# Beacon_controller_ESP32.net
KiCad netlist of a schematic drawn in EAGLE
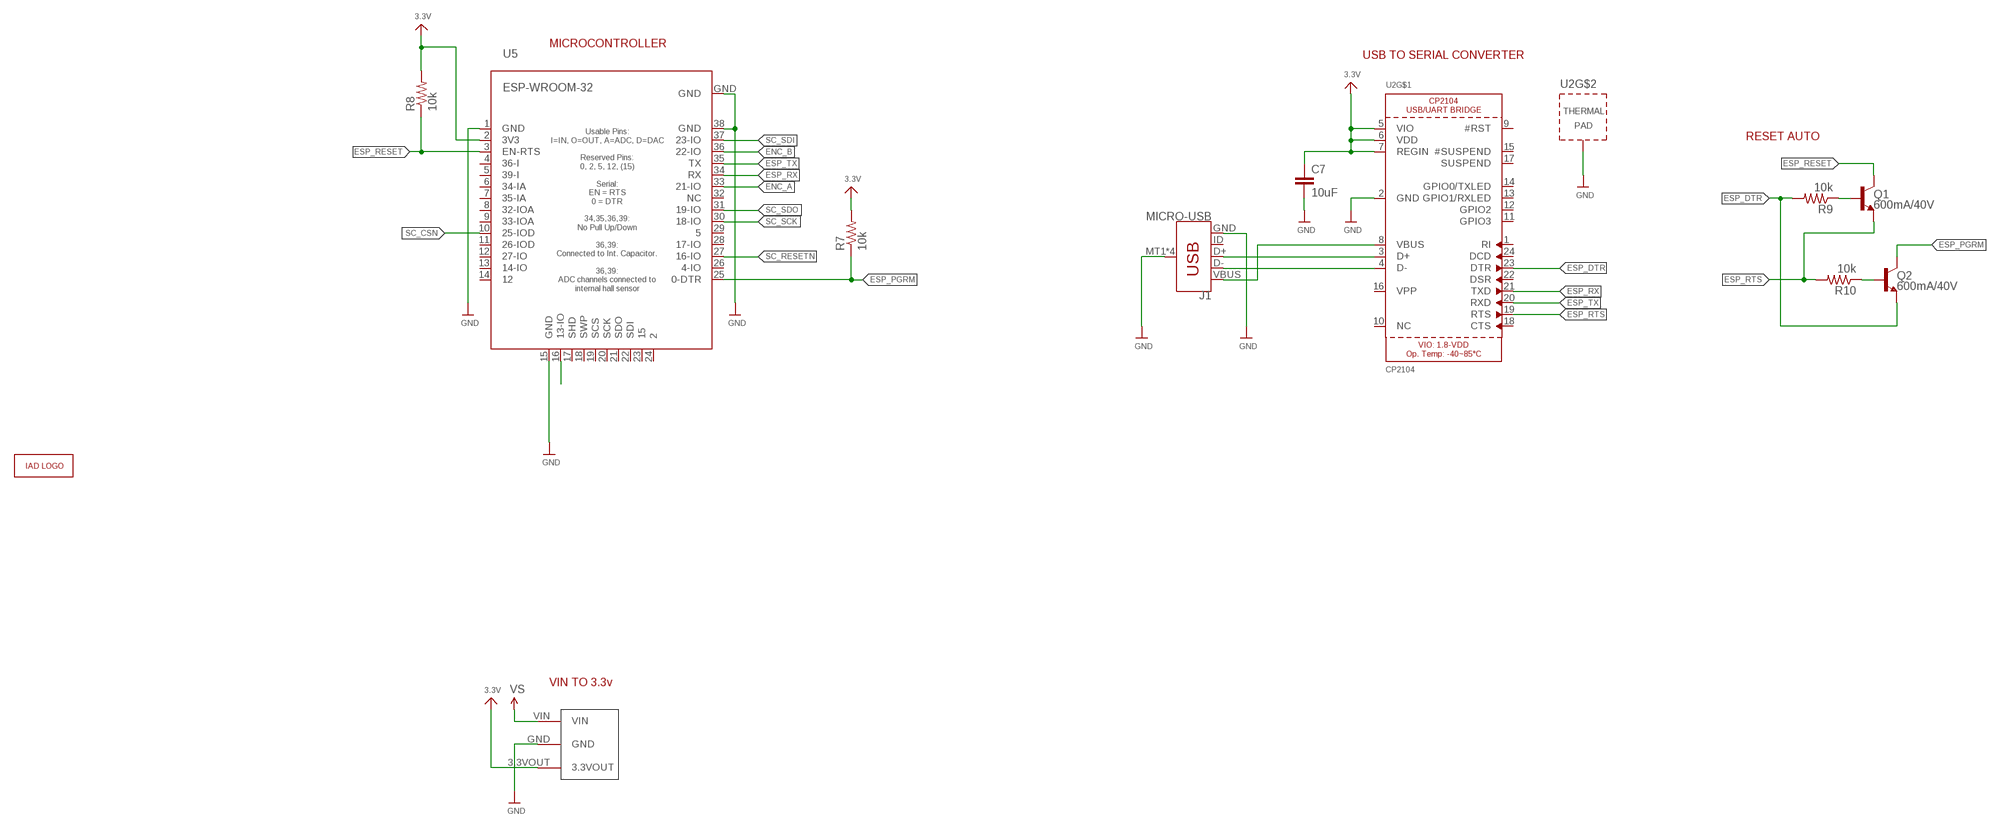
[diagram p0: schematic, sheet 1]

(export (version "E")
  (design (tool "Eeschema 10.0.6"))
  (components
    (comp (ref "A1")
      (value "ZHDK_LOGO_METAL")
      (footprint "eagle-import:ZHDK_LOGO")
      (libsource (lib "eagle-import") (part "ZHDK_LOGO_METAL"))
    )
    (comp (ref "C7")
      (value "10uF")
      (footprint "eagle-import:0603")
      (libsource (lib "eagle-import") (part "10UF-0603-6.3V-20%"))
    )
    (comp (ref "J1")
      (value "MICRO-USB")
      (footprint "eagle-import:USB-MICROB")
      (libsource (lib "eagle-import") (part "USB_MICRO-B_SMT"))
    )
    (comp (ref "Q1")
      (value "600mA/40V")
      (footprint "eagle-import:SOT23-3")
      (libsource (lib "eagle-import") (part "TRANS_NPN-MMBT2222AL"))
    )
    (comp (ref "Q2")
      (value "600mA/40V")
      (footprint "eagle-import:SOT23-3")
      (libsource (lib "eagle-import") (part "TRANS_NPN-MMBT2222AL"))
    )
    (comp (ref "R7")
      (value "10k")
      (footprint "eagle-import:0603-RES")
      (libsource (lib "eagle-import") (part "RESISTOR0603-RES"))
    )
    (comp (ref "R8")
      (value "10k")
      (footprint "eagle-import:0603-RES")
      (libsource (lib "eagle-import") (part "RESISTOR0603-RES"))
    )
    (comp (ref "R9")
      (value "10k")
      (footprint "eagle-import:0603-RES")
      (libsource (lib "eagle-import") (part "RESISTOR0603-RES"))
    )
    (comp (ref "R10")
      (value "10k")
      (footprint "eagle-import:0603-RES")
      (libsource (lib "eagle-import") (part "RESISTOR0603-RES"))
    )
    (comp (ref "U2")
      (value "CP2104")
      (footprint "eagle-import:QFN24_4MM_SMSC")
      (libsource (lib "eagle-import") (part "CP2104"))
    )
    (comp (ref "U4")
      (value "TRACO12433")
      (footprint "eagle-import:TRACO12433")
      (libsource (lib "eagle-import") (part "TRACO12433"))
    )
    (comp (ref "U5")
      (value "ESP-WROOM-32")
      (footprint "eagle-import:ESP-WROOM-32")
      (libsource (lib "eagle-import") (part "ESP-WROOM-32"))
    )
  )
  (nets
    (net (code "1") (name "3.3V") (class "Default")
      (node (ref "C7") (pin "1") (pinfunction "1_1") (pintype "passive"))
      (node (ref "R7") (pin "2") (pinfunction "2_2") (pintype "passive"))
      (node (ref "R8") (pin "2") (pinfunction "2_2") (pintype "passive"))
      (node (ref "U2") (pin "5") (pinfunction "VIO_5") (pintype "power_in"))
      (node (ref "U2") (pin "6") (pinfunction "VDD_6") (pintype "power_in"))
      (node (ref "U2") (pin "7") (pinfunction "REGIN_7") (pintype "power_in"))
      (node (ref "U4") (pin "3.3VOUT") (pinfunction "3.3VOUT_3.3VOUT") (pintype "bidirectional"))
      (node (ref "U5") (pin "2") (pinfunction "3V3_2") (pintype "bidirectional"))
    )
    (net (code "2") (name "ENC_A") (class "Default")
      (node (ref "U5") (pin "33") (pinfunction "21-IO_33") (pintype "bidirectional"))
    )
    (net (code "3") (name "ENC_B") (class "Default")
      (node (ref "U5") (pin "36") (pinfunction "22-IO_36") (pintype "bidirectional"))
    )
    (net (code "4") (name "ESP_DTR") (class "Default")
      (node (ref "Q2") (pin "2") (pinfunction "E_2") (pintype "passive"))
      (node (ref "R9") (pin "2") (pinfunction "2_2") (pintype "passive"))
      (node (ref "U2") (pin "23") (pinfunction "DTR_23") (pintype "output"))
    )
    (net (code "5") (name "ESP_PGRM") (class "Default")
      (node (ref "Q2") (pin "3") (pinfunction "C_3") (pintype "passive"))
      (node (ref "R7") (pin "1") (pinfunction "1_1") (pintype "passive"))
      (node (ref "U5") (pin "25") (pinfunction "0-DTR_25") (pintype "bidirectional"))
    )
    (net (code "6") (name "ESP_RESET") (class "Default")
      (node (ref "Q1") (pin "3") (pinfunction "C_3") (pintype "passive"))
      (node (ref "R8") (pin "1") (pinfunction "1_1") (pintype "passive"))
      (node (ref "U5") (pin "3") (pinfunction "EN-RTS_3") (pintype "bidirectional"))
    )
    (net (code "7") (name "ESP_RTS") (class "Default")
      (node (ref "Q1") (pin "2") (pinfunction "E_2") (pintype "passive"))
      (node (ref "R10") (pin "2") (pinfunction "2_2") (pintype "passive"))
      (node (ref "U2") (pin "19") (pinfunction "RTS_19") (pintype "output"))
    )
    (net (code "8") (name "ESP_RX") (class "Default")
      (node (ref "U2") (pin "21") (pinfunction "TXD_21") (pintype "output"))
      (node (ref "U5") (pin "34") (pinfunction "RX_34") (pintype "bidirectional"))
    )
    (net (code "9") (name "ESP_TX") (class "Default")
      (node (ref "U2") (pin "20") (pinfunction "RXD_20") (pintype "input"))
      (node (ref "U5") (pin "35") (pinfunction "TX_35") (pintype "bidirectional"))
    )
    (net (code "10") (name "GND") (class "Default")
      (node (ref "C7") (pin "2") (pinfunction "2_2") (pintype "passive"))
      (node (ref "J1") (pin "GND") (pinfunction "GND_GND") (pintype "power_in"))
      (node (ref "J1") (pin "MT1") (pinfunction "SHIELD_MT1") (pintype "bidirectional"))
      (node (ref "J1") (pin "MT2") (pinfunction "SHIELD_MT2") (pintype "bidirectional"))
      (node (ref "J1") (pin "P$1") (pinfunction "SHIELD_P$1") (pintype "bidirectional"))
      (node (ref "J1") (pin "P$2") (pinfunction "SHIELD_P$2") (pintype "bidirectional"))
      (node (ref "U2") (pin "2") (pinfunction "GND_2") (pintype "power_in"))
      (node (ref "U2") (pin "THERM") (pinfunction "TP_THERM") (pintype "power_in"))
      (node (ref "U4") (pin "GND") (pinfunction "GND_GND") (pintype "bidirectional"))
      (node (ref "U5") (pin "1") (pinfunction "GND_1") (pintype "bidirectional"))
      (node (ref "U5") (pin "15") (pinfunction "GND_15") (pintype "bidirectional"))
      (node (ref "U5") (pin "38") (pinfunction "GND_38") (pintype "bidirectional"))
      (node (ref "U5") (pin "GND") (pinfunction "GND_GND") (pintype "bidirectional"))
    )
    (net (code "11") (name "Net-(Q1-B)") (class "Default")
      (node (ref "Q1") (pin "1") (pinfunction "B_1") (pintype "passive"))
      (node (ref "R9") (pin "1") (pinfunction "1_1") (pintype "passive"))
    )
    (net (code "12") (name "Net-(Q2-B)") (class "Default")
      (node (ref "Q2") (pin "1") (pinfunction "B_1") (pintype "passive"))
      (node (ref "R10") (pin "1") (pinfunction "1_1") (pintype "passive"))
    )
    (net (code "13") (name "Net-(U2A-D+)") (class "Default")
      (node (ref "J1") (pin "D+") (pinfunction "D+_D+") (pintype "bidirectional"))
      (node (ref "U2") (pin "3") (pinfunction "D+_3") (pintype "bidirectional"))
    )
    (net (code "14") (name "Net-(U2A-D-)") (class "Default")
      (node (ref "J1") (pin "D-") (pinfunction "D-_D-") (pintype "bidirectional"))
      (node (ref "U2") (pin "4") (pinfunction "D-_4") (pintype "bidirectional"))
    )
    (net (code "15") (name "Net-(U2A-VBUS)") (class "Default")
      (node (ref "J1") (pin "VBUS") (pinfunction "VBUS_VBUS") (pintype "power_in"))
      (node (ref "U2") (pin "8") (pinfunction "VBUS_8") (pintype "power_in"))
    )
    (net (code "16") (name "SC_CSN") (class "Default")
      (node (ref "U5") (pin "10") (pinfunction "25-IOD_10") (pintype "bidirectional"))
    )
    (net (code "17") (name "SC_RESETN") (class "Default")
      (node (ref "U5") (pin "27") (pinfunction "16-IO_27") (pintype "bidirectional"))
    )
    (net (code "18") (name "SC_SCK") (class "Default")
      (node (ref "U5") (pin "30") (pinfunction "18-IO_30") (pintype "bidirectional"))
    )
    (net (code "19") (name "SC_SDI") (class "Default")
      (node (ref "U5") (pin "37") (pinfunction "23-IO_37") (pintype "bidirectional"))
    )
    (net (code "20") (name "SC_SDO") (class "Default")
      (node (ref "U5") (pin "31") (pinfunction "19-IO_31") (pintype "bidirectional"))
    )
    (net (code "21") (name "VS") (class "Default")
      (node (ref "U4") (pin "VIN") (pinfunction "VIN_VIN") (pintype "bidirectional"))
    )
    (net (code "22") (name "unconnected-(J1-PadID)") (class "Default")
      (node (ref "J1") (pin "ID") (pinfunction "ID_ID") (pintype "bidirectional"))
    )
    (net (code "23") (name "unconnected-(U2A-#RST-Pad9)") (class "Default")
      (node (ref "U2") (pin "9") (pinfunction "#RST_9") (pintype "bidirectional"))
    )
    (net (code "24") (name "unconnected-(U2A-#SUSPEND-Pad15)") (class "Default")
      (node (ref "U2") (pin "15") (pinfunction "#SUSPEND_15") (pintype "output"))
    )
    (net (code "25") (name "unconnected-(U2A-CTS-Pad18)") (class "Default")
      (node (ref "U2") (pin "18") (pinfunction "CTS_18") (pintype "input"))
    )
    (net (code "26") (name "unconnected-(U2A-DCD-Pad24)") (class "Default")
      (node (ref "U2") (pin "24") (pinfunction "DCD_24") (pintype "input"))
    )
    (net (code "27") (name "unconnected-(U2A-DSR-Pad22)") (class "Default")
      (node (ref "U2") (pin "22") (pinfunction "DSR_22") (pintype "input"))
    )
    (net (code "28") (name "unconnected-(U2A-GPIO0{slash}TXLED-Pad14)") (class "Default")
      (node (ref "U2") (pin "14") (pinfunction "GPIO0/TXLED_14") (pintype "bidirectional"))
    )
    (net (code "29") (name "unconnected-(U2A-GPIO1{slash}RXLED-Pad13)") (class "Default")
      (node (ref "U2") (pin "13") (pinfunction "GPIO1/RXLED_13") (pintype "bidirectional"))
    )
    (net (code "30") (name "unconnected-(U2A-GPIO2-Pad12)") (class "Default")
      (node (ref "U2") (pin "12") (pinfunction "GPIO2_12") (pintype "bidirectional"))
    )
    (net (code "31") (name "unconnected-(U2A-GPIO3-Pad11)") (class "Default")
      (node (ref "U2") (pin "11") (pinfunction "GPIO3_11") (pintype "bidirectional"))
    )
    (net (code "32") (name "unconnected-(U2A-NC-Pad10)") (class "Default")
      (node (ref "U2") (pin "10") (pinfunction "NC_10") (pintype "no_connect"))
    )
    (net (code "33") (name "unconnected-(U2A-RI-Pad1)") (class "Default")
      (node (ref "U2") (pin "1") (pinfunction "RI_1") (pintype "input"))
    )
    (net (code "34") (name "unconnected-(U2A-SUSPEND-Pad17)") (class "Default")
      (node (ref "U2") (pin "17") (pinfunction "SUSPEND_17") (pintype "output"))
    )
    (net (code "35") (name "unconnected-(U2A-VPP-Pad16)") (class "Default")
      (node (ref "U2") (pin "16") (pinfunction "VPP_16") (pintype "bidirectional"))
    )
    (net (code "36") (name "unconnected-(U5-2-Pad24)") (class "Default")
      (node (ref "U5") (pin "24") (pinfunction "2_24") (pintype "bidirectional"))
    )
    (net (code "37") (name "unconnected-(U5-4-IO-Pad26)") (class "Default")
      (node (ref "U5") (pin "26") (pinfunction "4-IO_26") (pintype "bidirectional"))
    )
    (net (code "38") (name "unconnected-(U5-5-Pad29)") (class "Default")
      (node (ref "U5") (pin "29") (pinfunction "5_29") (pintype "bidirectional"))
    )
    (net (code "39") (name "unconnected-(U5-12-Pad14)") (class "Default")
      (node (ref "U5") (pin "14") (pinfunction "12_14") (pintype "bidirectional"))
    )
    (net (code "40") (name "unconnected-(U5-13-IO-Pad16)") (class "Default")
      (node (ref "U5") (pin "16") (pinfunction "13-IO_16") (pintype "bidirectional"))
    )
    (net (code "41") (name "unconnected-(U5-14-IO-Pad13)") (class "Default")
      (node (ref "U5") (pin "13") (pinfunction "14-IO_13") (pintype "bidirectional"))
    )
    (net (code "42") (name "unconnected-(U5-15-Pad23)") (class "Default")
      (node (ref "U5") (pin "23") (pinfunction "15_23") (pintype "bidirectional"))
    )
    (net (code "43") (name "unconnected-(U5-17-IO-Pad28)") (class "Default")
      (node (ref "U5") (pin "28") (pinfunction "17-IO_28") (pintype "bidirectional"))
    )
    (net (code "44") (name "unconnected-(U5-26-IOD-Pad11)") (class "Default")
      (node (ref "U5") (pin "11") (pinfunction "26-IOD_11") (pintype "bidirectional"))
    )
    (net (code "45") (name "unconnected-(U5-27-IO-Pad12)") (class "Default")
      (node (ref "U5") (pin "12") (pinfunction "27-IO_12") (pintype "bidirectional"))
    )
    (net (code "46") (name "unconnected-(U5-32-IOA-Pad8)") (class "Default")
      (node (ref "U5") (pin "8") (pinfunction "32-IOA_8") (pintype "bidirectional"))
    )
    (net (code "47") (name "unconnected-(U5-33-IOA-Pad9)") (class "Default")
      (node (ref "U5") (pin "9") (pinfunction "33-IOA_9") (pintype "bidirectional"))
    )
    (net (code "48") (name "unconnected-(U5-34-IA-Pad6)") (class "Default")
      (node (ref "U5") (pin "6") (pinfunction "34-IA_6") (pintype "bidirectional"))
    )
    (net (code "49") (name "unconnected-(U5-35-IA-Pad7)") (class "Default")
      (node (ref "U5") (pin "7") (pinfunction "35-IA_7") (pintype "bidirectional"))
    )
    (net (code "50") (name "unconnected-(U5-36-I-Pad4)") (class "Default")
      (node (ref "U5") (pin "4") (pinfunction "36-I_4") (pintype "bidirectional"))
    )
    (net (code "51") (name "unconnected-(U5-39-I-Pad5)") (class "Default")
      (node (ref "U5") (pin "5") (pinfunction "39-I_5") (pintype "bidirectional"))
    )
    (net (code "52") (name "unconnected-(U5-NC-Pad32)") (class "Default")
      (node (ref "U5") (pin "32") (pinfunction "NC_32") (pintype "bidirectional"))
    )
    (net (code "53") (name "unconnected-(U5-SCK-Pad20)") (class "Default")
      (node (ref "U5") (pin "20") (pinfunction "SCK_20") (pintype "bidirectional"))
    )
    (net (code "54") (name "unconnected-(U5-SCS-Pad19)") (class "Default")
      (node (ref "U5") (pin "19") (pinfunction "SCS_19") (pintype "bidirectional"))
    )
    (net (code "55") (name "unconnected-(U5-SDI-Pad22)") (class "Default")
      (node (ref "U5") (pin "22") (pinfunction "SDI_22") (pintype "bidirectional"))
    )
    (net (code "56") (name "unconnected-(U5-SDO-Pad21)") (class "Default")
      (node (ref "U5") (pin "21") (pinfunction "SDO_21") (pintype "bidirectional"))
    )
    (net (code "57") (name "unconnected-(U5-SHD-Pad17)") (class "Default")
      (node (ref "U5") (pin "17") (pinfunction "SHD_17") (pintype "bidirectional"))
    )
    (net (code "58") (name "unconnected-(U5-SWP-Pad18)") (class "Default")
      (node (ref "U5") (pin "18") (pinfunction "SWP_18") (pintype "bidirectional"))
    )
  )
)
